# main.net
KiCad netlist of a schematic drawn in EAGLE
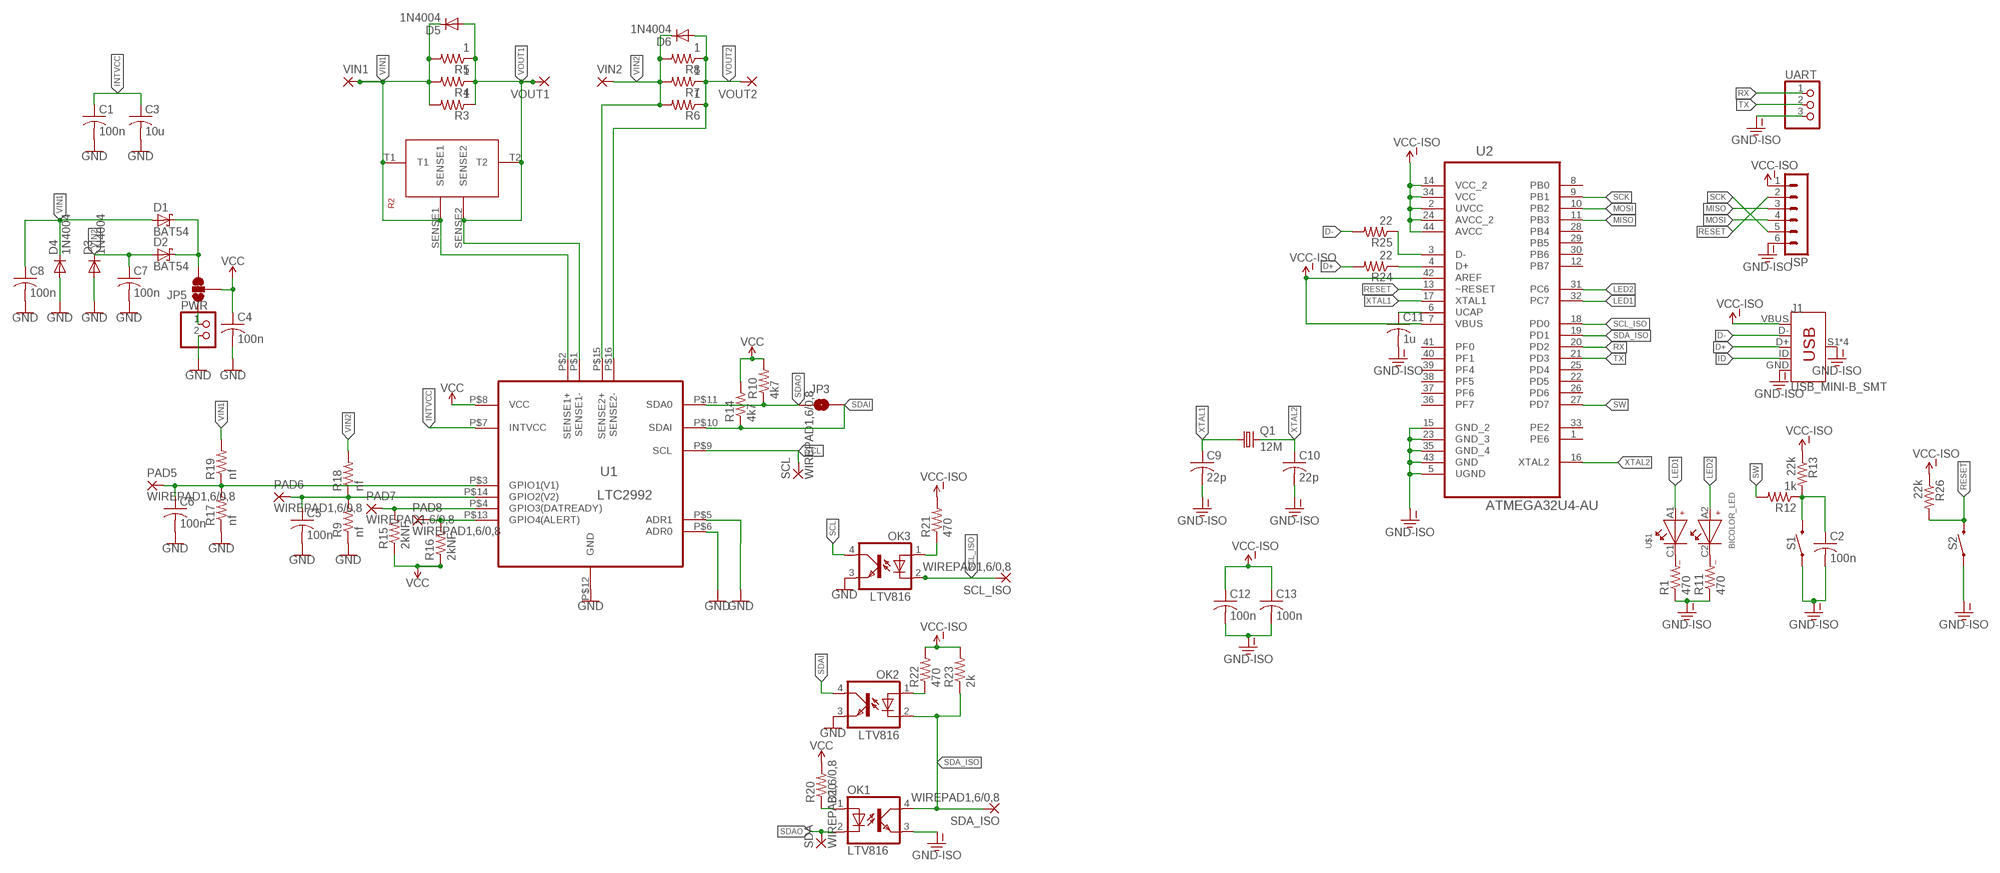
[diagram p0: schematic, sheet 1]

(export (version "E")
  (design (tool "Eeschema 10.0.6"))
  (components
    (comp (ref "C1")
      (value "100n")
      (footprint "eagle-import:C0603")
      (libsource (lib "eagle-import") (part "C-USC0603"))
    )
    (comp (ref "C2")
      (value "100n")
      (footprint "eagle-import:C0603")
      (libsource (lib "eagle-import") (part "C-USC0603"))
    )
    (comp (ref "C3")
      (value "10u")
      (footprint "eagle-import:C0603")
      (libsource (lib "eagle-import") (part "C-USC0603"))
    )
    (comp (ref "C4")
      (value "100n")
      (footprint "eagle-import:C0603")
      (libsource (lib "eagle-import") (part "C-USC0603"))
    )
    (comp (ref "C5")
      (value "100n")
      (footprint "eagle-import:C0603")
      (libsource (lib "eagle-import") (part "C-USC0603"))
    )
    (comp (ref "C6")
      (value "100n")
      (footprint "eagle-import:C0603")
      (libsource (lib "eagle-import") (part "C-USC0603"))
    )
    (comp (ref "C7")
      (value "100n")
      (footprint "eagle-import:C0603")
      (libsource (lib "eagle-import") (part "C-USC0603"))
    )
    (comp (ref "C8")
      (value "100n")
      (footprint "eagle-import:C0603")
      (libsource (lib "eagle-import") (part "C-USC0603"))
    )
    (comp (ref "C9")
      (value "22p")
      (footprint "eagle-import:C0603")
      (libsource (lib "eagle-import") (part "C-USC0603"))
    )
    (comp (ref "C10")
      (value "22p")
      (footprint "eagle-import:C0603")
      (libsource (lib "eagle-import") (part "C-USC0603"))
    )
    (comp (ref "C11")
      (value "1u")
      (footprint "eagle-import:C0603")
      (libsource (lib "eagle-import") (part "C-USC0603"))
    )
    (comp (ref "C12")
      (value "100n")
      (footprint "eagle-import:C0603")
      (libsource (lib "eagle-import") (part "C-USC0603"))
    )
    (comp (ref "C13")
      (value "100n")
      (footprint "eagle-import:C0603")
      (libsource (lib "eagle-import") (part "C-USC0603"))
    )
    (comp (ref "D1")
      (value "BAT54")
      (footprint "eagle-import:SOT23")
      (libsource (lib "eagle-import") (part "BAT54"))
    )
    (comp (ref "D2")
      (value "BAT54")
      (footprint "eagle-import:SOT23")
      (libsource (lib "eagle-import") (part "BAT54"))
    )
    (comp (ref "D3")
      (value "1N4004")
      (footprint "eagle-import:DO41-10")
      (libsource (lib "eagle-import") (part "1N4004"))
    )
    (comp (ref "D4")
      (value "1N4004")
      (footprint "eagle-import:DO41-10")
      (libsource (lib "eagle-import") (part "1N4004"))
    )
    (comp (ref "D5")
      (value "1N4004")
      (footprint "eagle-import:DO41-10")
      (libsource (lib "eagle-import") (part "1N4004"))
    )
    (comp (ref "D6")
      (value "1N4004")
      (footprint "eagle-import:DO41-10")
      (libsource (lib "eagle-import") (part "1N4004"))
    )
    (comp (ref "ISP")
      (value "MA06-1")
      (footprint "eagle-import:MA06-1")
      (libsource (lib "eagle-import") (part "MA06-1"))
    )
    (comp (ref "J1")
      (value "USB_MINI-B_SMT")
      (footprint "eagle-import:USB-MINIB")
      (libsource (lib "eagle-import") (part "USB_MINI-B_SMT"))
    )
    (comp (ref "JP3")
      (value "JUMPER-SMT_2_NO_SILK")
      (footprint "eagle-import:SMT-JUMPER_2_NO_SILK")
      (libsource (lib "eagle-import") (part "JUMPER-SMT_2_NO_SILK"))
    )
    (comp (ref "JP5")
      (value "JUMPER-SMT_3_1-NC_TRACE_NO-SILK")
      (footprint "eagle-import:SMT-JUMPER_3_1-NC_TRACE_NO-SILK")
      (libsource (lib "eagle-import") (part "JUMPER-SMT_3_1-NC_TRACE_NO-SILK"))
    )
    (comp (ref "OK1")
      (value "LTV816")
      (footprint "eagle-import:DIL04")
      (libsource (lib "eagle-import") (part "LTV816"))
    )
    (comp (ref "OK2")
      (value "LTV816")
      (footprint "eagle-import:DIL04")
      (libsource (lib "eagle-import") (part "LTV816"))
    )
    (comp (ref "OK3")
      (value "LTV816")
      (footprint "eagle-import:DIL04")
      (libsource (lib "eagle-import") (part "LTV816"))
    )
    (comp (ref "PAD5")
      (value "WIREPAD1,6/0,8")
      (footprint "eagle-import:1,6_0,8")
      (libsource (lib "eagle-import") (part "WIREPAD1,6/0,8"))
    )
    (comp (ref "PAD6")
      (value "WIREPAD1,6/0,8")
      (footprint "eagle-import:1,6_0,8")
      (libsource (lib "eagle-import") (part "WIREPAD1,6/0,8"))
    )
    (comp (ref "PAD7")
      (value "WIREPAD1,6/0,8")
      (footprint "eagle-import:1,6_0,8")
      (libsource (lib "eagle-import") (part "WIREPAD1,6/0,8"))
    )
    (comp (ref "PAD8")
      (value "WIREPAD1,6/0,8")
      (footprint "eagle-import:1,6_0,8")
      (libsource (lib "eagle-import") (part "WIREPAD1,6/0,8"))
    )
    (comp (ref "PWR")
      (value "PINHD-1X2")
      (footprint "eagle-import:1X02")
      (libsource (lib "eagle-import") (part "PINHD-1X2"))
    )
    (comp (ref "Q1")
      (value "12M")
      (footprint "eagle-import:HC49_S")
      (libsource (lib "eagle-import") (part "CRYSTALHC49S"))
    )
    (comp (ref "R1")
      (value "470")
      (footprint "eagle-import:R0603")
      (libsource (lib "eagle-import") (part "R-US_R0603"))
    )
    (comp (ref "R2")
      (value "30m")
      (footprint "eagle-import:CSR2TTE30L0F")
      (libsource (lib "eagle-import") (part "CSR2TTE30L0F"))
    )
    (comp (ref "R3")
      (value "1")
      (footprint "eagle-import:0309_12")
      (libsource (lib "eagle-import") (part "R-US_0309/12"))
    )
    (comp (ref "R4")
      (value "1")
      (footprint "eagle-import:M1206")
      (libsource (lib "eagle-import") (part "R-US_M1206"))
    )
    (comp (ref "R5")
      (value "1")
      (footprint "eagle-import:R0603")
      (libsource (lib "eagle-import") (part "R-US_R0603"))
    )
    (comp (ref "R6")
      (value "1")
      (footprint "eagle-import:0309_12")
      (libsource (lib "eagle-import") (part "R-US_0309/12"))
    )
    (comp (ref "R7")
      (value "1")
      (footprint "eagle-import:M1206")
      (libsource (lib "eagle-import") (part "R-US_M1206"))
    )
    (comp (ref "R8")
      (value "1")
      (footprint "eagle-import:R0603")
      (libsource (lib "eagle-import") (part "R-US_R0603"))
    )
    (comp (ref "R9")
      (value "nf")
      (footprint "eagle-import:R0603")
      (libsource (lib "eagle-import") (part "R-US_R0603"))
    )
    (comp (ref "R10")
      (value "4k7")
      (footprint "eagle-import:R0603")
      (libsource (lib "eagle-import") (part "R-US_R0603"))
    )
    (comp (ref "R11")
      (value "470")
      (footprint "eagle-import:R0603")
      (libsource (lib "eagle-import") (part "R-US_R0603"))
    )
    (comp (ref "R12")
      (value "1k")
      (footprint "eagle-import:R0603")
      (libsource (lib "eagle-import") (part "R-US_R0603"))
    )
    (comp (ref "R13")
      (value "22k")
      (footprint "eagle-import:R0603")
      (libsource (lib "eagle-import") (part "R-US_R0603"))
    )
    (comp (ref "R14")
      (value "4k7")
      (footprint "eagle-import:R0603")
      (libsource (lib "eagle-import") (part "R-US_R0603"))
    )
    (comp (ref "R15")
      (value "2kNF")
      (footprint "eagle-import:R0603")
      (libsource (lib "eagle-import") (part "R-US_R0603"))
    )
    (comp (ref "R16")
      (value "2kNF")
      (footprint "eagle-import:R0603")
      (libsource (lib "eagle-import") (part "R-US_R0603"))
    )
    (comp (ref "R17")
      (value "nf")
      (footprint "eagle-import:R0603")
      (libsource (lib "eagle-import") (part "R-US_R0603"))
    )
    (comp (ref "R18")
      (value "nf")
      (footprint "eagle-import:R0603")
      (libsource (lib "eagle-import") (part "R-US_R0603"))
    )
    (comp (ref "R19")
      (value "nf")
      (footprint "eagle-import:R0603")
      (libsource (lib "eagle-import") (part "R-US_R0603"))
    )
    (comp (ref "R20")
      (value "820")
      (footprint "eagle-import:R0603")
      (libsource (lib "eagle-import") (part "R-US_R0603"))
    )
    (comp (ref "R21")
      (value "470")
      (footprint "eagle-import:R0603")
      (libsource (lib "eagle-import") (part "R-US_R0603"))
    )
    (comp (ref "R22")
      (value "470")
      (footprint "eagle-import:R0603")
      (libsource (lib "eagle-import") (part "R-US_R0603"))
    )
    (comp (ref "R23")
      (value "2k")
      (footprint "eagle-import:R0603")
      (libsource (lib "eagle-import") (part "R-US_R0603"))
    )
    (comp (ref "R24")
      (value "22")
      (footprint "eagle-import:R0603")
      (libsource (lib "eagle-import") (part "R-US_R0603"))
    )
    (comp (ref "R25")
      (value "22")
      (footprint "eagle-import:R0603")
      (libsource (lib "eagle-import") (part "R-US_R0603"))
    )
    (comp (ref "R26")
      (value "22k")
      (footprint "eagle-import:R0603")
      (libsource (lib "eagle-import") (part "R-US_R0603"))
    )
    (comp (ref "S1")
      (value "MOMENTARY-SWITCH-SPST-PTH-6.0MM-KIT")
      (footprint "eagle-import:TACTILE_SWITCH_PTH_6.0MM_KIT")
      (libsource (lib "eagle-import") (part "MOMENTARY-SWITCH-SPST-PTH-6.0MM-KIT"))
    )
    (comp (ref "S2")
      (value "MOMENTARY-SWITCH-SPST-PTH-6.0MM-KIT")
      (footprint "eagle-import:TACTILE_SWITCH_PTH_6.0MM_KIT")
      (libsource (lib "eagle-import") (part "MOMENTARY-SWITCH-SPST-PTH-6.0MM-KIT"))
    )
    (comp (ref "SCL")
      (value "WIREPAD1,6/0,8")
      (footprint "eagle-import:1,6_0,8")
      (libsource (lib "eagle-import") (part "WIREPAD1,6/0,8"))
    )
    (comp (ref "SCL_ISO")
      (value "WIREPAD1,6/0,8")
      (footprint "eagle-import:1,6_0,8")
      (libsource (lib "eagle-import") (part "WIREPAD1,6/0,8"))
    )
    (comp (ref "SDA")
      (value "WIREPAD1,6/0,8")
      (footprint "eagle-import:1,6_0,8")
      (libsource (lib "eagle-import") (part "WIREPAD1,6/0,8"))
    )
    (comp (ref "SDA_ISO")
      (value "WIREPAD1,6/0,8")
      (footprint "eagle-import:1,6_0,8")
      (libsource (lib "eagle-import") (part "WIREPAD1,6/0,8"))
    )
    (comp (ref "U$1")
      (value "BICOLOR_LED")
      (footprint "eagle-import:BICOLOR_LED")
      (libsource (lib "eagle-import") (part "BICOLOR_LED"))
    )
    (comp (ref "U1")
      (value "LTC2992")
      (footprint "eagle-import:MSOP_16")
      (libsource (lib "eagle-import") (part "LTC2992"))
    )
    (comp (ref "U2")
      (value "ATMEGA32U4-AU")
      (footprint "eagle-import:QFP80P1200X1200X120-44N")
      (libsource (lib "eagle-import") (part "ATMEGA32U4-AU"))
    )
    (comp (ref "UART")
      (value "PINHD-1X3")
      (footprint "eagle-import:1X03")
      (libsource (lib "eagle-import") (part "PINHD-1X3"))
    )
    (comp (ref "VIN1")
      (value "2,54/0,8")
      (footprint "eagle-import:2,54_0,8")
      (libsource (lib "eagle-import") (part "2,54/0,8"))
    )
    (comp (ref "VIN2")
      (value "2,54/0,8")
      (footprint "eagle-import:2,54_0,8")
      (libsource (lib "eagle-import") (part "2,54/0,8"))
    )
    (comp (ref "VOUT1")
      (value "2,54/0,8")
      (footprint "eagle-import:2,54_0,8")
      (libsource (lib "eagle-import") (part "2,54/0,8"))
    )
    (comp (ref "VOUT2")
      (value "2,54/0,8")
      (footprint "eagle-import:2,54_0,8")
      (libsource (lib "eagle-import") (part "2,54/0,8"))
    )
  )
  (nets
    (net (code "1") (name "D+") (class "Default")
      (node (ref "J1") (pin "D+") (pinfunction "D+_D+") (pintype "bidirectional"))
      (node (ref "R24") (pin "2") (pinfunction "2_2") (pintype "passive"))
    )
    (net (code "2") (name "D-") (class "Default")
      (node (ref "J1") (pin "D-") (pinfunction "D-_D-") (pintype "bidirectional"))
      (node (ref "R25") (pin "2") (pinfunction "2_2") (pintype "passive"))
    )
    (net (code "3") (name "GND") (class "Default")
      (node (ref "C1") (pin "2") (pinfunction "2_2") (pintype "passive"))
      (node (ref "C3") (pin "2") (pinfunction "2_2") (pintype "passive"))
      (node (ref "C4") (pin "2") (pinfunction "2_2") (pintype "passive"))
      (node (ref "C5") (pin "2") (pinfunction "2_2") (pintype "passive"))
      (node (ref "C6") (pin "2") (pinfunction "2_2") (pintype "passive"))
      (node (ref "C7") (pin "2") (pinfunction "2_2") (pintype "passive"))
      (node (ref "C8") (pin "2") (pinfunction "2_2") (pintype "passive"))
      (node (ref "D3") (pin "A") (pinfunction "A_A") (pintype "passive"))
      (node (ref "D4") (pin "A") (pinfunction "A_A") (pintype "passive"))
      (node (ref "OK2") (pin "3") (pinfunction "EMIT_3") (pintype "passive"))
      (node (ref "OK3") (pin "3") (pinfunction "EMIT_3") (pintype "passive"))
      (node (ref "PWR") (pin "2") (pinfunction "2_2") (pintype "passive"))
      (node (ref "R17") (pin "1") (pinfunction "1_1") (pintype "passive"))
      (node (ref "R9") (pin "1") (pinfunction "1_1") (pintype "passive"))
      (node (ref "U1") (pin "P$12") (pinfunction "GND_P$12") (pintype "passive"))
      (node (ref "U1") (pin "P$5") (pinfunction "ADR1_P$5") (pintype "input"))
      (node (ref "U1") (pin "P$6") (pinfunction "ADR0_P$6") (pintype "input"))
    )
    (net (code "4") (name "GND-ISO") (class "Default")
      (node (ref "C10") (pin "2") (pinfunction "2_2") (pintype "passive"))
      (node (ref "C11") (pin "2") (pinfunction "2_2") (pintype "passive"))
      (node (ref "C12") (pin "2") (pinfunction "2_2") (pintype "passive"))
      (node (ref "C13") (pin "2") (pinfunction "2_2") (pintype "passive"))
      (node (ref "C2") (pin "2") (pinfunction "2_2") (pintype "passive"))
      (node (ref "C9") (pin "2") (pinfunction "2_2") (pintype "passive"))
      (node (ref "ISP") (pin "6") (pinfunction "6_6") (pintype "passive"))
      (node (ref "J1") (pin "GND") (pinfunction "GND_GND") (pintype "power_in"))
      (node (ref "J1") (pin "S1") (pinfunction "SHIELD_S1") (pintype "bidirectional"))
      (node (ref "J1") (pin "S2") (pinfunction "SHIELD_S2") (pintype "bidirectional"))
      (node (ref "J1") (pin "S3") (pinfunction "SHIELD_S3") (pintype "bidirectional"))
      (node (ref "J1") (pin "S4") (pinfunction "SHIELD_S4") (pintype "bidirectional"))
      (node (ref "OK1") (pin "3") (pinfunction "EMIT_3") (pintype "passive"))
      (node (ref "R1") (pin "1") (pinfunction "1_1") (pintype "passive"))
      (node (ref "R11") (pin "1") (pinfunction "1_1") (pintype "passive"))
      (node (ref "S1") (pin "1") (pinfunction "1_1") (pintype "passive"))
      (node (ref "S2") (pin "1") (pinfunction "1_1") (pintype "passive"))
      (node (ref "U2") (pin "15") (pinfunction "GND_2_15") (pintype "passive"))
      (node (ref "U2") (pin "23") (pinfunction "GND_3_23") (pintype "passive"))
      (node (ref "U2") (pin "35") (pinfunction "GND_4_35") (pintype "passive"))
      (node (ref "U2") (pin "43") (pinfunction "GND_43") (pintype "passive"))
      (node (ref "U2") (pin "5") (pinfunction "UGND_5") (pintype "passive"))
      (node (ref "UART") (pin "3") (pinfunction "3_3") (pintype "passive"))
    )
    (net (code "5") (name "ID") (class "Default")
      (node (ref "J1") (pin "ID") (pinfunction "ID_ID") (pintype "bidirectional"))
    )
    (net (code "6") (name "INTVCC") (class "Default")
      (node (ref "C1") (pin "1") (pinfunction "1_1") (pintype "passive"))
      (node (ref "C3") (pin "1") (pinfunction "1_1") (pintype "passive"))
      (node (ref "U1") (pin "P$7") (pinfunction "INTVCC_P$7") (pintype "bidirectional"))
    )
    (net (code "7") (name "LED1") (class "Default")
      (node (ref "U$1") (pin "A1") (pinfunction "A1_A1") (pintype "passive"))
      (node (ref "U2") (pin "32") (pinfunction "PC7_32") (pintype "bidirectional"))
    )
    (net (code "8") (name "LED2") (class "Default")
      (node (ref "U$1") (pin "A2") (pinfunction "A2_A2") (pintype "passive"))
      (node (ref "U2") (pin "31") (pinfunction "PC6_31") (pintype "bidirectional"))
    )
    (net (code "9") (name "MISO") (class "Default")
      (node (ref "ISP") (pin "3") (pinfunction "3_3") (pintype "passive"))
      (node (ref "U2") (pin "11") (pinfunction "PB3_11") (pintype "bidirectional"))
    )
    (net (code "10") (name "MOSI") (class "Default")
      (node (ref "ISP") (pin "4") (pinfunction "4_4") (pintype "passive"))
      (node (ref "U2") (pin "10") (pinfunction "PB2_10") (pintype "bidirectional"))
    )
    (net (code "11") (name "Net-(D1-C)") (class "Default")
      (node (ref "D1") (pin "3") (pinfunction "C_3") (pintype "passive"))
      (node (ref "D2") (pin "3") (pinfunction "C_3") (pintype "passive"))
      (node (ref "JP5") (pin "3") (pinfunction "3_3") (pintype "passive"))
    )
    (net (code "12") (name "Net-(JP5-Pad1)") (class "Default")
      (node (ref "JP5") (pin "1") (pinfunction "1_1") (pintype "passive"))
      (node (ref "PWR") (pin "1") (pinfunction "1_1") (pintype "passive"))
    )
    (net (code "13") (name "Net-(OK1-A)") (class "Default")
      (node (ref "OK1") (pin "1") (pinfunction "A_1") (pintype "passive"))
      (node (ref "R20") (pin "1") (pinfunction "1_1") (pintype "passive"))
    )
    (net (code "14") (name "Net-(OK2-A)") (class "Default")
      (node (ref "OK2") (pin "1") (pinfunction "A_1") (pintype "passive"))
      (node (ref "R22") (pin "1") (pinfunction "1_1") (pintype "passive"))
    )
    (net (code "15") (name "Net-(OK3-A)") (class "Default")
      (node (ref "OK3") (pin "1") (pinfunction "A_1") (pintype "passive"))
      (node (ref "R21") (pin "1") (pinfunction "1_1") (pintype "passive"))
    )
    (net (code "16") (name "Net-(PAD5-P)") (class "Default")
      (node (ref "C6") (pin "1") (pinfunction "1_1") (pintype "passive"))
      (node (ref "PAD5") (pin "1") (pinfunction "P_1") (pintype "passive"))
      (node (ref "R17") (pin "2") (pinfunction "2_2") (pintype "passive"))
      (node (ref "R19") (pin "1") (pinfunction "1_1") (pintype "passive"))
      (node (ref "U1") (pin "P$3") (pinfunction "GPIO1(V1)_P$3") (pintype "input"))
    )
    (net (code "17") (name "Net-(PAD6-P)") (class "Default")
      (node (ref "C5") (pin "1") (pinfunction "1_1") (pintype "passive"))
      (node (ref "PAD6") (pin "1") (pinfunction "P_1") (pintype "passive"))
      (node (ref "R18") (pin "1") (pinfunction "1_1") (pintype "passive"))
      (node (ref "R9") (pin "2") (pinfunction "2_2") (pintype "passive"))
      (node (ref "U1") (pin "P$14") (pinfunction "GPIO2(V2)_P$14") (pintype "input"))
    )
    (net (code "18") (name "Net-(PAD7-P)") (class "Default")
      (node (ref "PAD7") (pin "1") (pinfunction "P_1") (pintype "passive"))
      (node (ref "R15") (pin "2") (pinfunction "2_2") (pintype "passive"))
      (node (ref "U1") (pin "P$4") (pinfunction "GPIO3(DATREADY)_P$4") (pintype "input"))
    )
    (net (code "19") (name "Net-(PAD8-P)") (class "Default")
      (node (ref "PAD8") (pin "1") (pinfunction "P_1") (pintype "passive"))
      (node (ref "R16") (pin "2") (pinfunction "2_2") (pintype "passive"))
      (node (ref "U1") (pin "P$13") (pinfunction "GPIO4(ALERT)_P$13") (pintype "input"))
    )
    (net (code "20") (name "Net-(R1-Pad2)") (class "Default")
      (node (ref "R1") (pin "2") (pinfunction "2_2") (pintype "passive"))
      (node (ref "U$1") (pin "C1") (pinfunction "C1_C1") (pintype "passive"))
    )
    (net (code "21") (name "Net-(R11-Pad2)") (class "Default")
      (node (ref "R11") (pin "2") (pinfunction "2_2") (pintype "passive"))
      (node (ref "U$1") (pin "C2") (pinfunction "C2_C2") (pintype "passive"))
    )
    (net (code "22") (name "Net-(S1-2)") (class "Default")
      (node (ref "C2") (pin "1") (pinfunction "1_1") (pintype "passive"))
      (node (ref "R12") (pin "1") (pinfunction "1_1") (pintype "passive"))
      (node (ref "R13") (pin "2") (pinfunction "2_2") (pintype "passive"))
      (node (ref "S1") (pin "3") (pinfunction "2_3") (pintype "passive"))
    )
    (net (code "23") (name "Net-(U2-D+)") (class "Default")
      (node (ref "R24") (pin "1") (pinfunction "1_1") (pintype "passive"))
      (node (ref "U2") (pin "4") (pinfunction "D+_4") (pintype "passive"))
    )
    (net (code "24") (name "Net-(U2-D-)") (class "Default")
      (node (ref "R25") (pin "1") (pinfunction "1_1") (pintype "passive"))
      (node (ref "U2") (pin "3") (pinfunction "D-_3") (pintype "passive"))
    )
    (net (code "25") (name "Net-(U2-UCAP)") (class "Default")
      (node (ref "C11") (pin "1") (pinfunction "1_1") (pintype "passive"))
      (node (ref "U2") (pin "6") (pinfunction "UCAP_6") (pintype "power_in"))
    )
    (net (code "26") (name "RESET") (class "Default")
      (node (ref "ISP") (pin "2") (pinfunction "2_2") (pintype "passive"))
      (node (ref "R26") (pin "2") (pinfunction "2_2") (pintype "passive"))
      (node (ref "S2") (pin "3") (pinfunction "2_3") (pintype "passive"))
      (node (ref "U2") (pin "13") (pinfunction "~{RESET}_13") (pintype "input"))
    )
    (net (code "27") (name "RX") (class "Default")
      (node (ref "U2") (pin "20") (pinfunction "PD2_20") (pintype "bidirectional"))
      (node (ref "UART") (pin "1") (pinfunction "1_1") (pintype "passive"))
    )
    (net (code "28") (name "SCK") (class "Default")
      (node (ref "ISP") (pin "5") (pinfunction "5_5") (pintype "passive"))
      (node (ref "U2") (pin "9") (pinfunction "PB1_9") (pintype "bidirectional"))
    )
    (net (code "29") (name "SCL") (class "Default")
      (node (ref "OK3") (pin "4") (pinfunction "COL_4") (pintype "passive"))
      (node (ref "SCL") (pin "1") (pinfunction "P_1") (pintype "passive"))
      (node (ref "U1") (pin "P$9") (pinfunction "SCL_P$9") (pintype "input"))
    )
    (net (code "30") (name "SCL_ISO") (class "Default")
      (node (ref "OK3") (pin "2") (pinfunction "C_2") (pintype "passive"))
      (node (ref "SCL_ISO") (pin "1") (pinfunction "P_1") (pintype "passive"))
      (node (ref "U2") (pin "18") (pinfunction "PD0_18") (pintype "bidirectional"))
    )
    (net (code "31") (name "SDAI") (class "Default")
      (node (ref "JP3") (pin "2") (pinfunction "2_2") (pintype "passive"))
      (node (ref "OK2") (pin "4") (pinfunction "COL_4") (pintype "passive"))
      (node (ref "R14") (pin "1") (pinfunction "1_1") (pintype "passive"))
      (node (ref "U1") (pin "P$10") (pinfunction "SDAI_P$10") (pintype "bidirectional"))
    )
    (net (code "32") (name "SDAO") (class "Default")
      (node (ref "JP3") (pin "1") (pinfunction "1_1") (pintype "passive"))
      (node (ref "OK1") (pin "2") (pinfunction "C_2") (pintype "passive"))
      (node (ref "R10") (pin "1") (pinfunction "1_1") (pintype "passive"))
      (node (ref "SDA") (pin "1") (pinfunction "P_1") (pintype "passive"))
      (node (ref "U1") (pin "P$11") (pinfunction "SDA0_P$11") (pintype "bidirectional"))
    )
    (net (code "33") (name "SDA_ISO") (class "Default")
      (node (ref "OK1") (pin "4") (pinfunction "COL_4") (pintype "passive"))
      (node (ref "OK2") (pin "2") (pinfunction "C_2") (pintype "passive"))
      (node (ref "R23") (pin "1") (pinfunction "1_1") (pintype "passive"))
      (node (ref "SDA_ISO") (pin "1") (pinfunction "P_1") (pintype "passive"))
      (node (ref "U2") (pin "19") (pinfunction "PD1_19") (pintype "bidirectional"))
    )
    (net (code "34") (name "SW") (class "Default")
      (node (ref "R12") (pin "2") (pinfunction "2_2") (pintype "passive"))
      (node (ref "U2") (pin "27") (pinfunction "PD7_27") (pintype "bidirectional"))
    )
    (net (code "35") (name "TX") (class "Default")
      (node (ref "U2") (pin "21") (pinfunction "PD3_21") (pintype "bidirectional"))
      (node (ref "UART") (pin "2") (pinfunction "2_2") (pintype "passive"))
    )
    (net (code "36") (name "VCC") (class "Default")
      (node (ref "C4") (pin "1") (pinfunction "1_1") (pintype "passive"))
      (node (ref "JP5") (pin "2") (pinfunction "2_2") (pintype "passive"))
      (node (ref "R10") (pin "2") (pinfunction "2_2") (pintype "passive"))
      (node (ref "R14") (pin "2") (pinfunction "2_2") (pintype "passive"))
      (node (ref "R15") (pin "1") (pinfunction "1_1") (pintype "passive"))
      (node (ref "R16") (pin "1") (pinfunction "1_1") (pintype "passive"))
      (node (ref "R20") (pin "2") (pinfunction "2_2") (pintype "passive"))
      (node (ref "U1") (pin "P$8") (pinfunction "VCC_P$8") (pintype "power_in"))
    )
    (net (code "37") (name "VCC-ISO") (class "Default")
      (node (ref "C12") (pin "1") (pinfunction "1_1") (pintype "passive"))
      (node (ref "C13") (pin "1") (pinfunction "1_1") (pintype "passive"))
      (node (ref "ISP") (pin "1") (pinfunction "1_1") (pintype "passive"))
      (node (ref "J1") (pin "VBUS") (pinfunction "VBUS_VBUS") (pintype "power_in"))
      (node (ref "R13") (pin "1") (pinfunction "1_1") (pintype "passive"))
      (node (ref "R21") (pin "2") (pinfunction "2_2") (pintype "passive"))
      (node (ref "R22") (pin "2") (pinfunction "2_2") (pintype "passive"))
      (node (ref "R23") (pin "2") (pinfunction "2_2") (pintype "passive"))
      (node (ref "R26") (pin "1") (pinfunction "1_1") (pintype "passive"))
      (node (ref "U2") (pin "14") (pinfunction "VCC_2_14") (pintype "power_in"))
      (node (ref "U2") (pin "2") (pinfunction "UVCC_2") (pintype "power_in"))
      (node (ref "U2") (pin "24") (pinfunction "AVCC_2_24") (pintype "power_in"))
      (node (ref "U2") (pin "34") (pinfunction "VCC_34") (pintype "power_in"))
      (node (ref "U2") (pin "42") (pinfunction "AREF_42") (pintype "input"))
      (node (ref "U2") (pin "44") (pinfunction "AVCC_44") (pintype "power_in"))
      (node (ref "U2") (pin "7") (pinfunction "VBUS_7") (pintype "input"))
    )
    (net (code "38") (name "VIN1") (class "Default")
      (node (ref "C8") (pin "1") (pinfunction "1_1") (pintype "passive"))
      (node (ref "D1") (pin "1") (pinfunction "A_1") (pintype "passive"))
      (node (ref "D4") (pin "C") (pinfunction "C_C") (pintype "passive"))
      (node (ref "D5") (pin "C") (pinfunction "C_C") (pintype "passive"))
      (node (ref "R19") (pin "2") (pinfunction "2_2") (pintype "passive"))
      (node (ref "R2") (pin "SENSE1") (pinfunction "SENSE1_SENSE1") (pintype "bidirectional"))
      (node (ref "R2") (pin "T1") (pinfunction "T1_T1") (pintype "bidirectional"))
      (node (ref "R3") (pin "2") (pinfunction "2_2") (pintype "passive"))
      (node (ref "R4") (pin "2") (pinfunction "2_2") (pintype "passive"))
      (node (ref "R5") (pin "2") (pinfunction "2_2") (pintype "passive"))
      (node (ref "U1") (pin "P$2") (pinfunction "SENSE1+_P$2") (pintype "bidirectional"))
      (node (ref "VIN1") (pin "1") (pinfunction "P_1") (pintype "passive"))
    )
    (net (code "39") (name "VIN2") (class "Default")
      (node (ref "C7") (pin "1") (pinfunction "1_1") (pintype "passive"))
      (node (ref "D2") (pin "1") (pinfunction "A_1") (pintype "passive"))
      (node (ref "D3") (pin "C") (pinfunction "C_C") (pintype "passive"))
      (node (ref "D6") (pin "C") (pinfunction "C_C") (pintype "passive"))
      (node (ref "R18") (pin "2") (pinfunction "2_2") (pintype "passive"))
      (node (ref "R6") (pin "2") (pinfunction "2_2") (pintype "passive"))
      (node (ref "R7") (pin "2") (pinfunction "2_2") (pintype "passive"))
      (node (ref "R8") (pin "2") (pinfunction "2_2") (pintype "passive"))
      (node (ref "U1") (pin "P$15") (pinfunction "SENSE2+_P$15") (pintype "bidirectional"))
      (node (ref "VIN2") (pin "1") (pinfunction "P_1") (pintype "passive"))
    )
    (net (code "40") (name "VOUT1") (class "Default")
      (node (ref "D5") (pin "A") (pinfunction "A_A") (pintype "passive"))
      (node (ref "R2") (pin "SENSE2") (pinfunction "SENSE2_SENSE2") (pintype "bidirectional"))
      (node (ref "R2") (pin "T2") (pinfunction "T2_T2") (pintype "bidirectional"))
      (node (ref "R3") (pin "1") (pinfunction "1_1") (pintype "passive"))
      (node (ref "R4") (pin "1") (pinfunction "1_1") (pintype "passive"))
      (node (ref "R5") (pin "1") (pinfunction "1_1") (pintype "passive"))
      (node (ref "U1") (pin "P$1") (pinfunction "SENSE1-_P$1") (pintype "bidirectional"))
      (node (ref "VOUT1") (pin "1") (pinfunction "P_1") (pintype "passive"))
    )
    (net (code "41") (name "VOUT2") (class "Default")
      (node (ref "D6") (pin "A") (pinfunction "A_A") (pintype "passive"))
      (node (ref "R6") (pin "1") (pinfunction "1_1") (pintype "passive"))
      (node (ref "R7") (pin "1") (pinfunction "1_1") (pintype "passive"))
      (node (ref "R8") (pin "1") (pinfunction "1_1") (pintype "passive"))
      (node (ref "U1") (pin "P$16") (pinfunction "SENSE2-_P$16") (pintype "bidirectional"))
      (node (ref "VOUT2") (pin "1") (pinfunction "P_1") (pintype "passive"))
    )
    (net (code "42") (name "XTAL1") (class "Default")
      (node (ref "C9") (pin "1") (pinfunction "1_1") (pintype "passive"))
      (node (ref "Q1") (pin "1") (pinfunction "1_1") (pintype "passive"))
      (node (ref "U2") (pin "17") (pinfunction "XTAL1_17") (pintype "input"))
    )
    (net (code "43") (name "XTAL2") (class "Default")
      (node (ref "C10") (pin "1") (pinfunction "1_1") (pintype "passive"))
      (node (ref "Q1") (pin "2") (pinfunction "2_2") (pintype "passive"))
      (node (ref "U2") (pin "16") (pinfunction "XTAL2_16") (pintype "output"))
    )
    (net (code "44") (name "unconnected-(U2-PB0-Pad8)") (class "Default")
      (node (ref "U2") (pin "8") (pinfunction "PB0_8") (pintype "bidirectional"))
    )
    (net (code "45") (name "unconnected-(U2-PB4-Pad28)") (class "Default")
      (node (ref "U2") (pin "28") (pinfunction "PB4_28") (pintype "bidirectional"))
    )
    (net (code "46") (name "unconnected-(U2-PB5-Pad29)") (class "Default")
      (node (ref "U2") (pin "29") (pinfunction "PB5_29") (pintype "bidirectional"))
    )
    (net (code "47") (name "unconnected-(U2-PB6-Pad30)") (class "Default")
      (node (ref "U2") (pin "30") (pinfunction "PB6_30") (pintype "bidirectional"))
    )
    (net (code "48") (name "unconnected-(U2-PB7-Pad12)") (class "Default")
      (node (ref "U2") (pin "12") (pinfunction "PB7_12") (pintype "bidirectional"))
    )
    (net (code "49") (name "unconnected-(U2-PD4-Pad25)") (class "Default")
      (node (ref "U2") (pin "25") (pinfunction "PD4_25") (pintype "bidirectional"))
    )
    (net (code "50") (name "unconnected-(U2-PD5-Pad22)") (class "Default")
      (node (ref "U2") (pin "22") (pinfunction "PD5_22") (pintype "bidirectional"))
    )
    (net (code "51") (name "unconnected-(U2-PD6-Pad26)") (class "Default")
      (node (ref "U2") (pin "26") (pinfunction "PD6_26") (pintype "bidirectional"))
    )
    (net (code "52") (name "unconnected-(U2-PE2-Pad33)") (class "Default")
      (node (ref "U2") (pin "33") (pinfunction "PE2_33") (pintype "bidirectional"))
    )
    (net (code "53") (name "unconnected-(U2-PE6-Pad1)") (class "Default")
      (node (ref "U2") (pin "1") (pinfunction "PE6_1") (pintype "bidirectional"))
    )
    (net (code "54") (name "unconnected-(U2-PF0-Pad41)") (class "Default")
      (node (ref "U2") (pin "41") (pinfunction "PF0_41") (pintype "bidirectional"))
    )
    (net (code "55") (name "unconnected-(U2-PF1-Pad40)") (class "Default")
      (node (ref "U2") (pin "40") (pinfunction "PF1_40") (pintype "bidirectional"))
    )
    (net (code "56") (name "unconnected-(U2-PF4-Pad39)") (class "Default")
      (node (ref "U2") (pin "39") (pinfunction "PF4_39") (pintype "bidirectional"))
    )
    (net (code "57") (name "unconnected-(U2-PF5-Pad38)") (class "Default")
      (node (ref "U2") (pin "38") (pinfunction "PF5_38") (pintype "bidirectional"))
    )
    (net (code "58") (name "unconnected-(U2-PF6-Pad37)") (class "Default")
      (node (ref "U2") (pin "37") (pinfunction "PF6_37") (pintype "bidirectional"))
    )
    (net (code "59") (name "unconnected-(U2-PF7-Pad36)") (class "Default")
      (node (ref "U2") (pin "36") (pinfunction "PF7_36") (pintype "bidirectional"))
    )
  )
)
